# MB_Control.net
KiCad netlist of a schematic drawn in Altium Designer
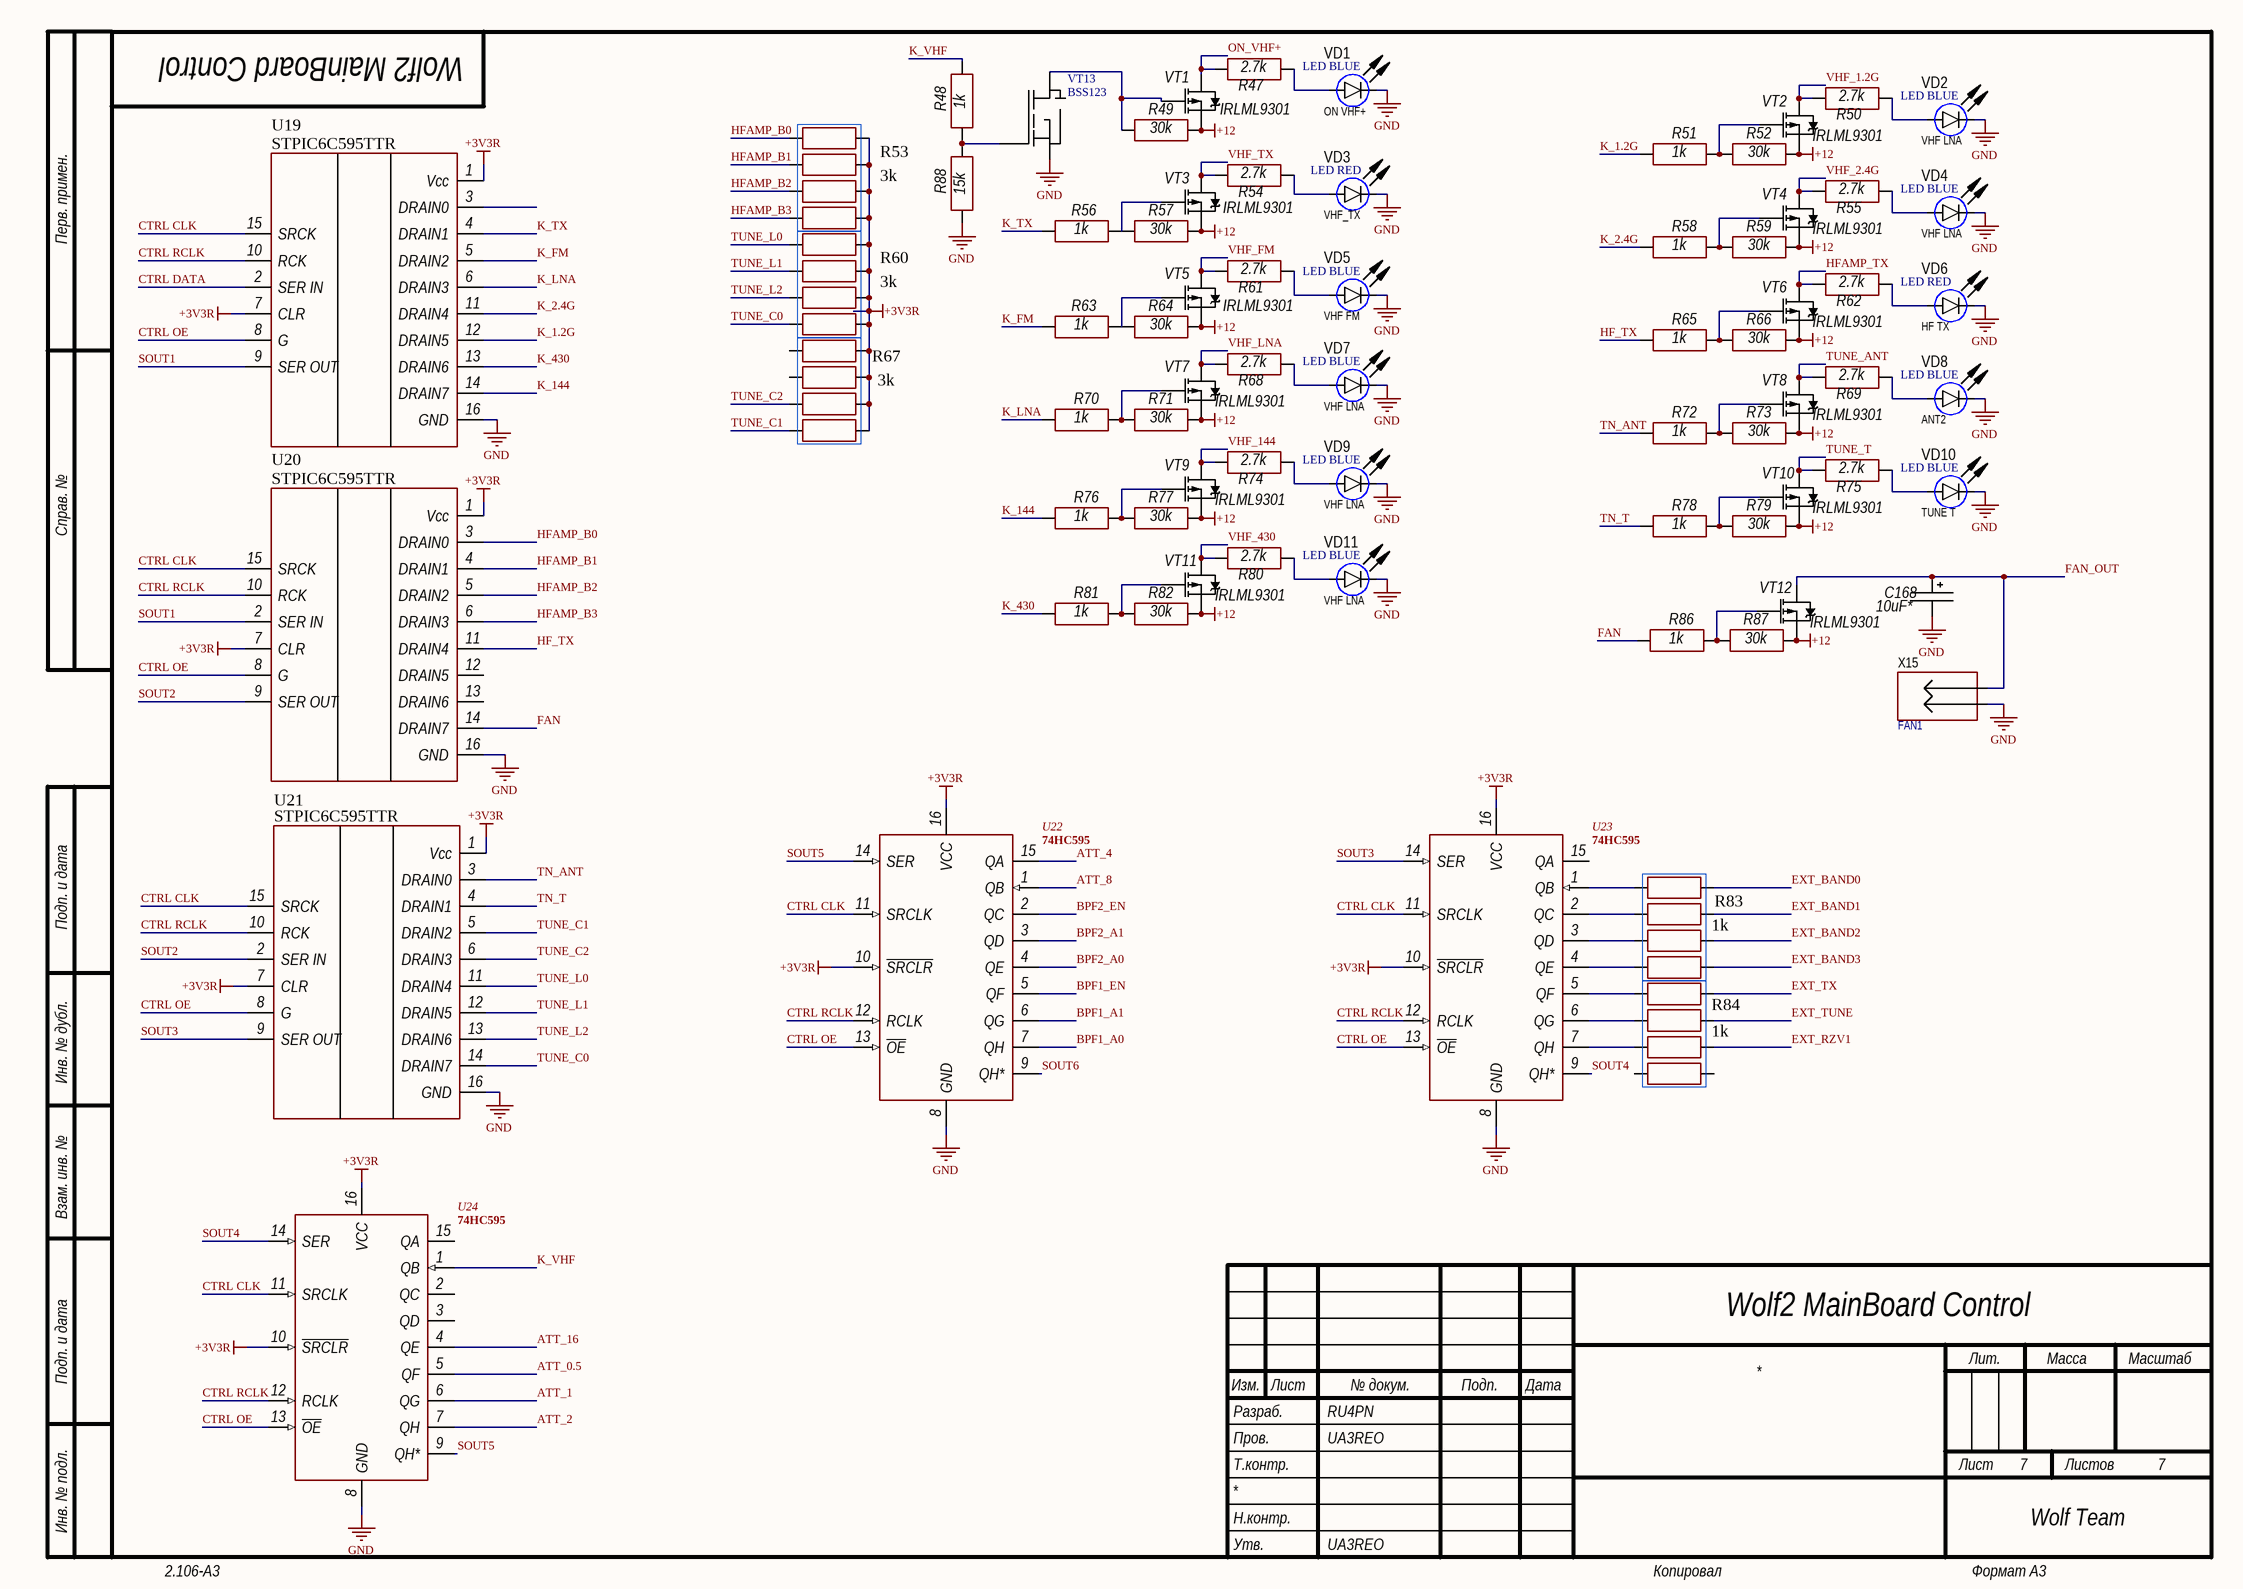
[diagram p0: MB_Control.SchDoc]

(export (version "E")
  (design (tool "Eeschema 10.0.6"))
  (components
    (comp (ref "C168")
      (value "10uF*")
      (footprint "standard:TANTAL_B")
      (libsource (lib "Discrete") (part "TantalCap"))
    )
    (comp (ref "R47")
      (value "2.7k")
      (footprint "standard:CH0805R")
      (libsource (lib "Discrete") (part "Resistor"))
    )
    (comp (ref "R48") (value "1k") (footprint "standard:CH0805R") (libsource (lib "") (part "Resistor_1")))
    (comp (ref "R49")
      (value "30k")
      (footprint "standard:CH0805R")
      (libsource (lib "Discrete") (part "Resistor"))
    )
    (comp (ref "R50")
      (value "2.7k")
      (footprint "standard:CH0805R")
      (libsource (lib "Discrete") (part "Resistor"))
    )
    (comp (ref "R51")
      (value "1k")
      (footprint "standard:CH0805R")
      (libsource (lib "Discrete") (part "Resistor"))
    )
    (comp (ref "R52")
      (value "30k")
      (footprint "standard:CH0805R")
      (libsource (lib "Discrete") (part "Resistor"))
    )
    (comp (ref "R53") (value "3k") (footprint "CAT16") (libsource (lib "") (part "CAT10-0804_1")))
    (comp (ref "R54")
      (value "2.7k")
      (footprint "standard:CH0805R")
      (libsource (lib "Discrete") (part "Resistor"))
    )
    (comp (ref "R55")
      (value "2.7k")
      (footprint "standard:CH0805R")
      (libsource (lib "Discrete") (part "Resistor"))
    )
    (comp (ref "R56")
      (value "1k")
      (footprint "standard:CH0805R")
      (libsource (lib "Discrete") (part "Resistor"))
    )
    (comp (ref "R57")
      (value "30k")
      (footprint "standard:CH0805R")
      (libsource (lib "Discrete") (part "Resistor"))
    )
    (comp (ref "R58")
      (value "1k")
      (footprint "standard:CH0805R")
      (libsource (lib "Discrete") (part "Resistor"))
    )
    (comp (ref "R59")
      (value "30k")
      (footprint "standard:CH0805R")
      (libsource (lib "Discrete") (part "Resistor"))
    )
    (comp (ref "R60") (value "3k") (footprint "CAT16") (libsource (lib "Discrete") (part "CAT10-0804")))
    (comp (ref "R61")
      (value "2.7k")
      (footprint "standard:CH0805R")
      (libsource (lib "Discrete") (part "Resistor"))
    )
    (comp (ref "R62")
      (value "2.7k")
      (footprint "standard:CH0805R")
      (libsource (lib "Discrete") (part "Resistor"))
    )
    (comp (ref "R63")
      (value "1k")
      (footprint "standard:CH0805R")
      (libsource (lib "Discrete") (part "Resistor"))
    )
    (comp (ref "R64")
      (value "30k")
      (footprint "standard:CH0805R")
      (libsource (lib "Discrete") (part "Resistor"))
    )
    (comp (ref "R65")
      (value "1k")
      (footprint "standard:CH0805R")
      (libsource (lib "Discrete") (part "Resistor"))
    )
    (comp (ref "R66")
      (value "30k")
      (footprint "standard:CH0805R")
      (libsource (lib "Discrete") (part "Resistor"))
    )
    (comp (ref "R67") (value "3k") (footprint "CAT16") (libsource (lib "") (part "CAT10-0804_1")))
    (comp (ref "R68")
      (value "2.7k")
      (footprint "standard:CH0805R")
      (libsource (lib "Discrete") (part "Resistor"))
    )
    (comp (ref "R69")
      (value "2.7k")
      (footprint "standard:CH0805R")
      (libsource (lib "Discrete") (part "Resistor"))
    )
    (comp (ref "R70")
      (value "1k")
      (footprint "standard:CH0805R")
      (libsource (lib "Discrete") (part "Resistor"))
    )
    (comp (ref "R71")
      (value "30k")
      (footprint "standard:CH0805R")
      (libsource (lib "Discrete") (part "Resistor"))
    )
    (comp (ref "R72")
      (value "1k")
      (footprint "standard:CH0805R")
      (libsource (lib "Discrete") (part "Resistor"))
    )
    (comp (ref "R73")
      (value "30k")
      (footprint "standard:CH0805R")
      (libsource (lib "Discrete") (part "Resistor"))
    )
    (comp (ref "R74")
      (value "2.7k")
      (footprint "standard:CH0805R")
      (libsource (lib "Discrete") (part "Resistor"))
    )
    (comp (ref "R75")
      (value "2.7k")
      (footprint "standard:CH0805R")
      (libsource (lib "Discrete") (part "Resistor"))
    )
    (comp (ref "R76")
      (value "1k")
      (footprint "standard:CH0805R")
      (libsource (lib "Discrete") (part "Resistor"))
    )
    (comp (ref "R77")
      (value "30k")
      (footprint "standard:CH0805R")
      (libsource (lib "Discrete") (part "Resistor"))
    )
    (comp (ref "R78")
      (value "1k")
      (footprint "standard:CH0805R")
      (libsource (lib "Discrete") (part "Resistor"))
    )
    (comp (ref "R79")
      (value "30k")
      (footprint "standard:CH0805R")
      (libsource (lib "Discrete") (part "Resistor"))
    )
    (comp (ref "R80")
      (value "2.7k")
      (footprint "standard:CH0805R")
      (libsource (lib "Discrete") (part "Resistor"))
    )
    (comp (ref "R81")
      (value "1k")
      (footprint "standard:CH0805R")
      (libsource (lib "Discrete") (part "Resistor"))
    )
    (comp (ref "R82")
      (value "30k")
      (footprint "standard:CH0805R")
      (libsource (lib "Discrete") (part "Resistor"))
    )
    (comp (ref "R83") (value "1k") (footprint "CAT16") (libsource (lib "") (part "CAT10-0804_1")))
    (comp (ref "R84") (value "1k") (footprint "CAT16") (libsource (lib "") (part "CAT10-0804_1")))
    (comp (ref "R86")
      (value "1k")
      (footprint "standard:CH0805R")
      (libsource (lib "Discrete") (part "Resistor"))
    )
    (comp (ref "R87")
      (value "30k")
      (footprint "standard:CH0805R")
      (libsource (lib "Discrete") (part "Resistor"))
    )
    (comp (ref "R88") (value "15k") (footprint "standard:CH0805R") (libsource (lib "") (part "Resistor_1")))
    (comp (ref "U19")
      (value "STPIC6C595TTR")
      (footprint "16-TSOP")
      (libsource (lib "") (part "STPIC6C595TTR_1"))
    )
    (comp (ref "U20")
      (value "STPIC6C595TTR")
      (footprint "16-TSOP")
      (libsource (lib "Digital") (part "STPIC6C595TTR"))
    )
    (comp (ref "U21")
      (value "STPIC6C595TTR")
      (footprint "16-TSOP")
      (libsource (lib "Digital") (part "STPIC6C595TTR"))
    )
    (comp (ref "U22") (value "74HC595") (footprint "16-SO") (libsource (lib "Digital") (part "HC595")))
    (comp (ref "U23") (value "74HC595") (footprint "16-SO") (libsource (lib "Digital") (part "HC595")))
    (comp (ref "U24") (value "74HC595") (footprint "16-SO") (libsource (lib "Digital") (part "HC595")))
    (comp (ref "VD1")
      (value "LED BLUE")
      (footprint "StandardCase:LED: 0805B")
      (fields
        (field (name "VALUEMANUFACTURERPARTNUMBER") "LED, *, *, *, -55...+150°C")
        (field (name "COLOR") "ON VHF+")
      )
      (libsource (lib "Diode") (part "LED_single"))
    )
    (comp (ref "VD2")
      (value "LED BLUE")
      (footprint "StandardCase:LED: 0805B")
      (fields
        (field (name "VALUEMANUFACTURERPARTNUMBER") "LED, *, *, *, -55...+150°C")
        (field (name "COLOR") "VHF LNA")
      )
      (libsource (lib "") (part "LED_single_2"))
    )
    (comp (ref "VD3")
      (value "LED RED")
      (footprint "StandardCase:LED: 0805R")
      (fields
        (field (name "VALUEMANUFACTURERPARTNUMBER") "LED, *, *, *, -55...+150°C")
        (field (name "COLOR") "VHF_TX")
      )
      (libsource (lib "Diode") (part "LED_single"))
    )
    (comp (ref "VD4")
      (value "LED BLUE")
      (footprint "StandardCase:LED: 0805B")
      (fields
        (field (name "VALUEMANUFACTURERPARTNUMBER") "LED, *, *, *, -55...+150°C")
        (field (name "COLOR") "VHF LNA")
      )
      (libsource (lib "") (part "LED_single_2"))
    )
    (comp (ref "VD5")
      (value "LED BLUE")
      (footprint "StandardCase:LED: 0805B")
      (fields
        (field (name "VALUEMANUFACTURERPARTNUMBER") "LED, *, *, *, -55...+150°C")
        (field (name "COLOR") "VHF FM")
      )
      (libsource (lib "Diode") (part "LED_single"))
    )
    (comp (ref "VD6")
      (value "LED RED")
      (footprint "StandardCase:LED: 0805R")
      (fields
        (field (name "VALUEMANUFACTURERPARTNUMBER") "LED, *, *, *, -55...+150°C")
        (field (name "COLOR") "HF TX")
      )
      (libsource (lib "") (part "LED_single_1"))
    )
    (comp (ref "VD7")
      (value "LED BLUE")
      (footprint "StandardCase:LED: 0805B")
      (fields
        (field (name "VALUEMANUFACTURERPARTNUMBER") "LED, *, *, *, -55...+150°C")
        (field (name "COLOR") "VHF LNA")
      )
      (libsource (lib "Diode") (part "LED_single"))
    )
    (comp (ref "VD8")
      (value "LED BLUE")
      (footprint "StandardCase:LED: 0805B")
      (fields
        (field (name "VALUEMANUFACTURERPARTNUMBER") "LED, *, *, *, -55...+150°C")
        (field (name "COLOR") "ANT2")
      )
      (libsource (lib "") (part "LED_single_2"))
    )
    (comp (ref "VD9")
      (value "LED BLUE")
      (footprint "StandardCase:LED: 0805B")
      (fields
        (field (name "VALUEMANUFACTURERPARTNUMBER") "LED, *, *, *, -55...+150°C")
        (field (name "COLOR") "VHF LNA")
      )
      (libsource (lib "Diode") (part "LED_single"))
    )
    (comp (ref "VD10")
      (value "LED BLUE")
      (footprint "StandardCase:LED: 0805B")
      (fields
        (field (name "VALUEMANUFACTURERPARTNUMBER") "LED, *, *, *, -55...+150°C")
        (field (name "COLOR") "TUNE T")
      )
      (libsource (lib "") (part "LED_single_2"))
    )
    (comp (ref "VD11")
      (value "LED BLUE")
      (footprint "StandardCase:LED: 0805B")
      (fields
        (field (name "VALUEMANUFACTURERPARTNUMBER") "LED, *, *, *, -55...+150°C")
        (field (name "COLOR") "VHF LNA")
      )
      (libsource (lib "Diode") (part "LED_single"))
    )
    (comp (ref "VT1")
      (value "IRLML9301")
      (footprint "standard:SOT23_132")
      (description "Mosfet")
      (libsource (lib "") (part "IRLML9301_1"))
    )
    (comp (ref "VT2")
      (value "IRLML9301")
      (footprint "standard:SOT23_132")
      (description "Mosfet")
      (libsource (lib "Transistor") (part "IRLML9301"))
    )
    (comp (ref "VT3")
      (value "IRLML9301")
      (footprint "standard:SOT23_132")
      (description "Mosfet")
      (libsource (lib "") (part "IRLML9301_1"))
    )
    (comp (ref "VT4")
      (value "IRLML9301")
      (footprint "standard:SOT23_132")
      (description "Mosfet")
      (libsource (lib "Transistor") (part "IRLML9301"))
    )
    (comp (ref "VT5")
      (value "IRLML9301")
      (footprint "standard:SOT23_132")
      (description "Mosfet")
      (libsource (lib "") (part "IRLML9301_1"))
    )
    (comp (ref "VT6")
      (value "IRLML9301")
      (footprint "standard:SOT23_132")
      (description "Mosfet")
      (libsource (lib "Transistor") (part "IRLML9301"))
    )
    (comp (ref "VT7")
      (value "IRLML9301")
      (footprint "standard:SOT23_132")
      (description "Mosfet")
      (libsource (lib "") (part "IRLML9301_1"))
    )
    (comp (ref "VT8")
      (value "IRLML9301")
      (footprint "standard:SOT23_132")
      (description "Mosfet")
      (libsource (lib "Transistor") (part "IRLML9301"))
    )
    (comp (ref "VT9")
      (value "IRLML9301")
      (footprint "standard:SOT23_132")
      (description "Mosfet")
      (libsource (lib "") (part "IRLML9301_1"))
    )
    (comp (ref "VT10")
      (value "IRLML9301")
      (footprint "standard:SOT23_132")
      (description "Mosfet")
      (libsource (lib "Transistor") (part "IRLML9301"))
    )
    (comp (ref "VT11")
      (value "IRLML9301")
      (footprint "standard:SOT23_132")
      (description "Mosfet")
      (libsource (lib "") (part "IRLML9301_1"))
    )
    (comp (ref "VT12")
      (value "IRLML9301")
      (footprint "standard:SOT23_132")
      (description "Mosfet")
      (libsource (lib "Transistor") (part "IRLML9301"))
    )
    (comp (ref "VT13")
      (value "BSS123")
      (footprint "SOT23_132")
      (libsource (lib "Transistor") (part "BSS123"))
    )
    (comp (ref "X15")
      (value "FAN1")
      (footprint "CON: CWF-2")
      (libsource (lib "Connectors") (part "Component-2pin"))
    )
  )
  (nets
    (net (code "1") (name "+3V3R") (class "Default")
      (node (ref "R53") (pin "5") (pinfunction "5_5") (pintype "passive"))
      (node (ref "R53") (pin "6") (pinfunction "6_6") (pintype "passive"))
      (node (ref "R53") (pin "7") (pinfunction "7_7") (pintype "passive"))
      (node (ref "R53") (pin "8") (pinfunction "8_8") (pintype "passive"))
      (node (ref "R60") (pin "5") (pinfunction "5_5") (pintype "passive"))
      (node (ref "R60") (pin "6") (pinfunction "6_6") (pintype "passive"))
      (node (ref "R60") (pin "7") (pinfunction "7_7") (pintype "passive"))
      (node (ref "R60") (pin "8") (pinfunction "8_8") (pintype "passive"))
      (node (ref "R67") (pin "5") (pinfunction "5_5") (pintype "passive"))
      (node (ref "R67") (pin "6") (pinfunction "6_6") (pintype "passive"))
      (node (ref "R67") (pin "7") (pinfunction "7_7") (pintype "passive"))
      (node (ref "R67") (pin "8") (pinfunction "8_8") (pintype "passive"))
      (node (ref "U19") (pin "1") (pinfunction "Vcc_1") (pintype "passive"))
      (node (ref "U19") (pin "7") (pinfunction "CLR_7") (pintype "passive"))
      (node (ref "U20") (pin "1") (pinfunction "Vcc_1") (pintype "passive"))
      (node (ref "U20") (pin "7") (pinfunction "CLR_7") (pintype "passive"))
      (node (ref "U21") (pin "1") (pinfunction "Vcc_1") (pintype "passive"))
      (node (ref "U21") (pin "7") (pinfunction "CLR_7") (pintype "passive"))
      (node (ref "U22") (pin "10") (pinfunction "~{SRCLR}_10") (pintype "input"))
      (node (ref "U22") (pin "16") (pinfunction "VCC_16") (pintype "passive"))
      (node (ref "U23") (pin "10") (pinfunction "~{SRCLR}_10") (pintype "input"))
      (node (ref "U23") (pin "16") (pinfunction "VCC_16") (pintype "passive"))
      (node (ref "U24") (pin "10") (pinfunction "~{SRCLR}_10") (pintype "input"))
      (node (ref "U24") (pin "16") (pinfunction "VCC_16") (pintype "passive"))
    )
    (net (code "2") (name "+12") (class "Default")
      (node (ref "R49") (pin "1") (pinfunction "1_1") (pintype "passive"))
      (node (ref "R52") (pin "1") (pinfunction "1_1") (pintype "passive"))
      (node (ref "R57") (pin "1") (pinfunction "1_1") (pintype "passive"))
      (node (ref "R59") (pin "1") (pinfunction "1_1") (pintype "passive"))
      (node (ref "R64") (pin "1") (pinfunction "1_1") (pintype "passive"))
      (node (ref "R66") (pin "1") (pinfunction "1_1") (pintype "passive"))
      (node (ref "R71") (pin "1") (pinfunction "1_1") (pintype "passive"))
      (node (ref "R73") (pin "1") (pinfunction "1_1") (pintype "passive"))
      (node (ref "R77") (pin "1") (pinfunction "1_1") (pintype "passive"))
      (node (ref "R79") (pin "1") (pinfunction "1_1") (pintype "passive"))
      (node (ref "R82") (pin "1") (pinfunction "1_1") (pintype "passive"))
      (node (ref "R87") (pin "1") (pinfunction "1_1") (pintype "passive"))
      (node (ref "VT1") (pin "2") (pinfunction "S_2") (pintype "passive"))
      (node (ref "VT10") (pin "2") (pinfunction "S_2") (pintype "passive"))
      (node (ref "VT11") (pin "2") (pinfunction "S_2") (pintype "passive"))
      (node (ref "VT12") (pin "2") (pinfunction "S_2") (pintype "passive"))
      (node (ref "VT2") (pin "2") (pinfunction "S_2") (pintype "passive"))
      (node (ref "VT3") (pin "2") (pinfunction "S_2") (pintype "passive"))
      (node (ref "VT4") (pin "2") (pinfunction "S_2") (pintype "passive"))
      (node (ref "VT5") (pin "2") (pinfunction "S_2") (pintype "passive"))
      (node (ref "VT6") (pin "2") (pinfunction "S_2") (pintype "passive"))
      (node (ref "VT7") (pin "2") (pinfunction "S_2") (pintype "passive"))
      (node (ref "VT8") (pin "2") (pinfunction "S_2") (pintype "passive"))
      (node (ref "VT9") (pin "2") (pinfunction "S_2") (pintype "passive"))
    )
    (net (code "3") (name "/ATT_0.5") (class "Default")
      (node (ref "U24") (pin "5") (pinfunction "QF_5") (pintype "passive"))
    )
    (net (code "4") (name "/ATT_1") (class "Default")
      (node (ref "U24") (pin "6") (pinfunction "QG_6") (pintype "passive"))
    )
    (net (code "5") (name "/ATT_2") (class "Default")
      (node (ref "U24") (pin "7") (pinfunction "QH_7") (pintype "passive"))
    )
    (net (code "6") (name "/ATT_4") (class "Default")
      (node (ref "U22") (pin "15") (pinfunction "QA_15") (pintype "passive"))
    )
    (net (code "7") (name "/ATT_8") (class "Default")
      (node (ref "U22") (pin "1") (pinfunction "QB_1") (pintype "input"))
    )
    (net (code "8") (name "/ATT_16") (class "Default")
      (node (ref "U24") (pin "4") (pinfunction "QE_4") (pintype "passive"))
    )
    (net (code "9") (name "/BPF1_A0") (class "Default")
      (node (ref "U22") (pin "7") (pinfunction "QH_7") (pintype "passive"))
    )
    (net (code "10") (name "/BPF1_A1") (class "Default")
      (node (ref "U22") (pin "6") (pinfunction "QG_6") (pintype "passive"))
    )
    (net (code "11") (name "/BPF1_EN") (class "Default")
      (node (ref "U22") (pin "5") (pinfunction "QF_5") (pintype "passive"))
    )
    (net (code "12") (name "/BPF2_A0") (class "Default")
      (node (ref "U22") (pin "4") (pinfunction "QE_4") (pintype "passive"))
    )
    (net (code "13") (name "/BPF2_A1") (class "Default")
      (node (ref "U22") (pin "3") (pinfunction "QD_3") (pintype "passive"))
    )
    (net (code "14") (name "/BPF2_EN") (class "Default")
      (node (ref "U22") (pin "2") (pinfunction "QC_2") (pintype "passive"))
    )
    (net (code "15") (name "/CTRL CLK") (class "Default")
      (node (ref "U19") (pin "15") (pinfunction "SRCK_15") (pintype "passive"))
      (node (ref "U20") (pin "15") (pinfunction "SRCK_15") (pintype "passive"))
      (node (ref "U21") (pin "15") (pinfunction "SRCK_15") (pintype "passive"))
      (node (ref "U22") (pin "11") (pinfunction "SRCLK_11") (pintype "input"))
      (node (ref "U23") (pin "11") (pinfunction "SRCLK_11") (pintype "input"))
      (node (ref "U24") (pin "11") (pinfunction "SRCLK_11") (pintype "input"))
    )
    (net (code "16") (name "/CTRL DATA") (class "Default")
      (node (ref "U19") (pin "2") (pinfunction "SER_IN_2") (pintype "passive"))
    )
    (net (code "17") (name "/CTRL OE") (class "Default")
      (node (ref "U19") (pin "8") (pinfunction "G_8") (pintype "passive"))
      (node (ref "U20") (pin "8") (pinfunction "G_8") (pintype "passive"))
      (node (ref "U21") (pin "8") (pinfunction "G_8") (pintype "passive"))
      (node (ref "U22") (pin "13") (pinfunction "~{OE}_13") (pintype "input"))
      (node (ref "U23") (pin "13") (pinfunction "~{OE}_13") (pintype "input"))
      (node (ref "U24") (pin "13") (pinfunction "~{OE}_13") (pintype "input"))
    )
    (net (code "18") (name "/CTRL RCLK") (class "Default")
      (node (ref "U19") (pin "10") (pinfunction "RCK_10") (pintype "passive"))
      (node (ref "U20") (pin "10") (pinfunction "RCK_10") (pintype "passive"))
      (node (ref "U21") (pin "10") (pinfunction "RCK_10") (pintype "passive"))
      (node (ref "U22") (pin "12") (pinfunction "RCLK_12") (pintype "input"))
      (node (ref "U23") (pin "12") (pinfunction "RCLK_12") (pintype "input"))
      (node (ref "U24") (pin "12") (pinfunction "RCLK_12") (pintype "input"))
    )
    (net (code "19") (name "/EXT_BAND0") (class "Default")
      (node (ref "R83") (pin "5") (pinfunction "5_5") (pintype "passive"))
    )
    (net (code "20") (name "/EXT_BAND1") (class "Default")
      (node (ref "R83") (pin "6") (pinfunction "6_6") (pintype "passive"))
    )
    (net (code "21") (name "/EXT_BAND2") (class "Default")
      (node (ref "R83") (pin "7") (pinfunction "7_7") (pintype "passive"))
    )
    (net (code "22") (name "/EXT_BAND3") (class "Default")
      (node (ref "R83") (pin "8") (pinfunction "8_8") (pintype "passive"))
    )
    (net (code "23") (name "/EXT_RZV1") (class "Default")
      (node (ref "R84") (pin "7") (pinfunction "7_7") (pintype "passive"))
    )
    (net (code "24") (name "/EXT_TUNE") (class "Default")
      (node (ref "R84") (pin "6") (pinfunction "6_6") (pintype "passive"))
    )
    (net (code "25") (name "/EXT_TX") (class "Default")
      (node (ref "R84") (pin "5") (pinfunction "5_5") (pintype "passive"))
    )
    (net (code "26") (name "/FAN") (class "Default")
      (node (ref "R86") (pin "2") (pinfunction "2_2") (pintype "passive"))
      (node (ref "U20") (pin "14") (pinfunction "DRAIN7_14") (pintype "passive"))
    )
    (net (code "27") (name "/FAN_OUT") (class "Default")
      (node (ref "C168") (pin "1") (pinfunction "1_1") (pintype "power_in"))
      (node (ref "VT12") (pin "3") (pinfunction "D_3") (pintype "passive"))
      (node (ref "X15") (pin "1") (pinfunction "1_1") (pintype "passive"))
    )
    (net (code "28") (name "/HFAMP_B0") (class "Default")
      (node (ref "R53") (pin "1") (pinfunction "1_1") (pintype "passive"))
      (node (ref "U20") (pin "3") (pinfunction "DRAIN0_3") (pintype "passive"))
    )
    (net (code "29") (name "/HFAMP_B1") (class "Default")
      (node (ref "R53") (pin "2") (pinfunction "2_2") (pintype "passive"))
      (node (ref "U20") (pin "4") (pinfunction "DRAIN1_4") (pintype "passive"))
    )
    (net (code "30") (name "/HFAMP_B2") (class "Default")
      (node (ref "R53") (pin "3") (pinfunction "3_3") (pintype "passive"))
      (node (ref "U20") (pin "5") (pinfunction "DRAIN2_5") (pintype "passive"))
    )
    (net (code "31") (name "/HFAMP_B3") (class "Default")
      (node (ref "R53") (pin "4") (pinfunction "4_4") (pintype "passive"))
      (node (ref "U20") (pin "6") (pinfunction "DRAIN3_6") (pintype "passive"))
    )
    (net (code "32") (name "/HFAMP_TX") (class "Default")
      (node (ref "R62") (pin "2") (pinfunction "2_2") (pintype "passive"))
      (node (ref "VT6") (pin "3") (pinfunction "D_3") (pintype "passive"))
    )
    (net (code "33") (name "/HF_TX") (class "Default")
      (node (ref "R65") (pin "2") (pinfunction "2_2") (pintype "passive"))
      (node (ref "U20") (pin "11") (pinfunction "DRAIN4_11") (pintype "passive"))
    )
    (net (code "34") (name "/K_1.2G") (class "Default")
      (node (ref "R51") (pin "2") (pinfunction "2_2") (pintype "passive"))
      (node (ref "U19") (pin "12") (pinfunction "DRAIN5_12") (pintype "passive"))
    )
    (net (code "35") (name "/K_2.4G") (class "Default")
      (node (ref "R58") (pin "2") (pinfunction "2_2") (pintype "passive"))
      (node (ref "U19") (pin "11") (pinfunction "DRAIN4_11") (pintype "passive"))
    )
    (net (code "36") (name "/K_144") (class "Default")
      (node (ref "R76") (pin "2") (pinfunction "2_2") (pintype "passive"))
      (node (ref "U19") (pin "14") (pinfunction "DRAIN7_14") (pintype "passive"))
    )
    (net (code "37") (name "/K_430") (class "Default")
      (node (ref "R81") (pin "2") (pinfunction "2_2") (pintype "passive"))
      (node (ref "U19") (pin "13") (pinfunction "DRAIN6_13") (pintype "passive"))
    )
    (net (code "38") (name "/K_FM") (class "Default")
      (node (ref "R63") (pin "2") (pinfunction "2_2") (pintype "passive"))
      (node (ref "U19") (pin "5") (pinfunction "DRAIN2_5") (pintype "passive"))
    )
    (net (code "39") (name "/K_LNA") (class "Default")
      (node (ref "R70") (pin "2") (pinfunction "2_2") (pintype "passive"))
      (node (ref "U19") (pin "6") (pinfunction "DRAIN3_6") (pintype "passive"))
    )
    (net (code "40") (name "/K_TX") (class "Default")
      (node (ref "R56") (pin "2") (pinfunction "2_2") (pintype "passive"))
      (node (ref "U19") (pin "4") (pinfunction "DRAIN1_4") (pintype "passive"))
    )
    (net (code "41") (name "/K_VHF") (class "Default")
      (node (ref "R48") (pin "1") (pinfunction "1_1") (pintype "passive"))
      (node (ref "U24") (pin "1") (pinfunction "QB_1") (pintype "input"))
    )
    (net (code "42") (name "/ON_VHF+") (class "Default")
      (node (ref "R47") (pin "2") (pinfunction "2_2") (pintype "passive"))
      (node (ref "VT1") (pin "3") (pinfunction "D_3") (pintype "passive"))
    )
    (net (code "43") (name "/SOUT1") (class "Default")
      (node (ref "U19") (pin "9") (pinfunction "SER_OUT_9") (pintype "passive"))
      (node (ref "U20") (pin "2") (pinfunction "SER_IN_2") (pintype "passive"))
    )
    (net (code "44") (name "/SOUT2") (class "Default")
      (node (ref "U20") (pin "9") (pinfunction "SER_OUT_9") (pintype "passive"))
      (node (ref "U21") (pin "2") (pinfunction "SER_IN_2") (pintype "passive"))
    )
    (net (code "45") (name "/SOUT3") (class "Default")
      (node (ref "U21") (pin "9") (pinfunction "SER_OUT_9") (pintype "passive"))
      (node (ref "U23") (pin "14") (pinfunction "SER_14") (pintype "input"))
    )
    (net (code "46") (name "/SOUT4") (class "Default")
      (node (ref "U23") (pin "9") (pinfunction "QH*_9") (pintype "passive"))
      (node (ref "U24") (pin "14") (pinfunction "SER_14") (pintype "input"))
    )
    (net (code "47") (name "/SOUT5") (class "Default")
      (node (ref "U22") (pin "14") (pinfunction "SER_14") (pintype "input"))
      (node (ref "U24") (pin "9") (pinfunction "QH*_9") (pintype "passive"))
    )
    (net (code "48") (name "/SOUT6") (class "Default")
      (node (ref "U22") (pin "9") (pinfunction "QH*_9") (pintype "passive"))
    )
    (net (code "49") (name "/TN_ANT") (class "Default")
      (node (ref "R72") (pin "2") (pinfunction "2_2") (pintype "passive"))
      (node (ref "U21") (pin "3") (pinfunction "DRAIN0_3") (pintype "passive"))
    )
    (net (code "50") (name "/TN_T") (class "Default")
      (node (ref "R78") (pin "2") (pinfunction "2_2") (pintype "passive"))
      (node (ref "U21") (pin "4") (pinfunction "DRAIN1_4") (pintype "passive"))
    )
    (net (code "51") (name "/TUNE_ANT") (class "Default")
      (node (ref "R69") (pin "2") (pinfunction "2_2") (pintype "passive"))
      (node (ref "VT8") (pin "3") (pinfunction "D_3") (pintype "passive"))
    )
    (net (code "52") (name "/TUNE_C0") (class "Default")
      (node (ref "R60") (pin "4") (pinfunction "4_4") (pintype "passive"))
      (node (ref "U21") (pin "14") (pinfunction "DRAIN7_14") (pintype "passive"))
    )
    (net (code "53") (name "/TUNE_C1") (class "Default")
      (node (ref "R67") (pin "4") (pinfunction "4_4") (pintype "passive"))
      (node (ref "U21") (pin "5") (pinfunction "DRAIN2_5") (pintype "passive"))
    )
    (net (code "54") (name "/TUNE_C2") (class "Default")
      (node (ref "R67") (pin "3") (pinfunction "3_3") (pintype "passive"))
      (node (ref "U21") (pin "6") (pinfunction "DRAIN3_6") (pintype "passive"))
    )
    (net (code "55") (name "/TUNE_L0") (class "Default")
      (node (ref "R60") (pin "1") (pinfunction "1_1") (pintype "passive"))
      (node (ref "U21") (pin "11") (pinfunction "DRAIN4_11") (pintype "passive"))
    )
    (net (code "56") (name "/TUNE_L1") (class "Default")
      (node (ref "R60") (pin "2") (pinfunction "2_2") (pintype "passive"))
      (node (ref "U21") (pin "12") (pinfunction "DRAIN5_12") (pintype "passive"))
    )
    (net (code "57") (name "/TUNE_L2") (class "Default")
      (node (ref "R60") (pin "3") (pinfunction "3_3") (pintype "passive"))
      (node (ref "U21") (pin "13") (pinfunction "DRAIN6_13") (pintype "passive"))
    )
    (net (code "58") (name "/TUNE_T") (class "Default")
      (node (ref "R75") (pin "2") (pinfunction "2_2") (pintype "passive"))
      (node (ref "VT10") (pin "3") (pinfunction "D_3") (pintype "passive"))
    )
    (net (code "59") (name "/VHF_1.2G") (class "Default")
      (node (ref "R50") (pin "2") (pinfunction "2_2") (pintype "passive"))
      (node (ref "VT2") (pin "3") (pinfunction "D_3") (pintype "passive"))
    )
    (net (code "60") (name "/VHF_2.4G") (class "Default")
      (node (ref "R55") (pin "2") (pinfunction "2_2") (pintype "passive"))
      (node (ref "VT4") (pin "3") (pinfunction "D_3") (pintype "passive"))
    )
    (net (code "61") (name "/VHF_144") (class "Default")
      (node (ref "R74") (pin "2") (pinfunction "2_2") (pintype "passive"))
      (node (ref "VT9") (pin "3") (pinfunction "D_3") (pintype "passive"))
    )
    (net (code "62") (name "/VHF_430") (class "Default")
      (node (ref "R80") (pin "2") (pinfunction "2_2") (pintype "passive"))
      (node (ref "VT11") (pin "3") (pinfunction "D_3") (pintype "passive"))
    )
    (net (code "63") (name "/VHF_FM") (class "Default")
      (node (ref "R61") (pin "2") (pinfunction "2_2") (pintype "passive"))
      (node (ref "VT5") (pin "3") (pinfunction "D_3") (pintype "passive"))
    )
    (net (code "64") (name "/VHF_LNA") (class "Default")
      (node (ref "R68") (pin "2") (pinfunction "2_2") (pintype "passive"))
      (node (ref "VT7") (pin "3") (pinfunction "D_3") (pintype "passive"))
    )
    (net (code "65") (name "/VHF_TX") (class "Default")
      (node (ref "R54") (pin "2") (pinfunction "2_2") (pintype "passive"))
      (node (ref "VT3") (pin "3") (pinfunction "D_3") (pintype "passive"))
    )
    (net (code "66") (name "GND") (class "Default")
      (node (ref "C168") (pin "2") (pinfunction "2_2") (pintype "power_in"))
      (node (ref "R88") (pin "2") (pinfunction "2_2") (pintype "passive"))
      (node (ref "U19") (pin "16") (pinfunction "GND_16") (pintype "passive"))
      (node (ref "U20") (pin "16") (pinfunction "GND_16") (pintype "passive"))
      (node (ref "U21") (pin "16") (pinfunction "GND_16") (pintype "passive"))
      (node (ref "U22") (pin "8") (pinfunction "GND_8") (pintype "passive"))
      (node (ref "U23") (pin "8") (pinfunction "GND_8") (pintype "passive"))
      (node (ref "U24") (pin "8") (pinfunction "GND_8") (pintype "passive"))
      (node (ref "VD1") (pin "2") (pinfunction "C_2") (pintype "passive"))
      (node (ref "VD10") (pin "2") (pinfunction "C_2") (pintype "passive"))
      (node (ref "VD11") (pin "2") (pinfunction "C_2") (pintype "passive"))
      (node (ref "VD2") (pin "2") (pinfunction "C_2") (pintype "passive"))
      (node (ref "VD3") (pin "2") (pinfunction "C_2") (pintype "passive"))
      (node (ref "VD4") (pin "2") (pinfunction "C_2") (pintype "passive"))
      (node (ref "VD5") (pin "2") (pinfunction "C_2") (pintype "passive"))
      (node (ref "VD6") (pin "2") (pinfunction "C_2") (pintype "passive"))
      (node (ref "VD7") (pin "2") (pinfunction "C_2") (pintype "passive"))
      (node (ref "VD8") (pin "2") (pinfunction "C_2") (pintype "passive"))
      (node (ref "VD9") (pin "2") (pinfunction "C_2") (pintype "passive"))
      (node (ref "VT13") (pin "2") (pinfunction "S_2") (pintype "passive"))
      (node (ref "X15") (pin "2") (pinfunction "2_2") (pintype "passive"))
    )
    (net (code "67") (name "Net-(U23-QB)") (class "Default")
      (node (ref "R83") (pin "1") (pinfunction "1_1") (pintype "passive"))
      (node (ref "U23") (pin "1") (pinfunction "QB_1") (pintype "input"))
    )
    (net (code "68") (name "Net-(U23-QC)") (class "Default")
      (node (ref "R83") (pin "2") (pinfunction "2_2") (pintype "passive"))
      (node (ref "U23") (pin "2") (pinfunction "QC_2") (pintype "passive"))
    )
    (net (code "69") (name "Net-(U23-QD)") (class "Default")
      (node (ref "R83") (pin "3") (pinfunction "3_3") (pintype "passive"))
      (node (ref "U23") (pin "3") (pinfunction "QD_3") (pintype "passive"))
    )
    (net (code "70") (name "Net-(U23-QE)") (class "Default")
      (node (ref "R83") (pin "4") (pinfunction "4_4") (pintype "passive"))
      (node (ref "U23") (pin "4") (pinfunction "QE_4") (pintype "passive"))
    )
    (net (code "71") (name "Net-(U23-QF)") (class "Default")
      (node (ref "R84") (pin "1") (pinfunction "1_1") (pintype "passive"))
      (node (ref "U23") (pin "5") (pinfunction "QF_5") (pintype "passive"))
    )
    (net (code "72") (name "Net-(U23-QG)") (class "Default")
      (node (ref "R84") (pin "2") (pinfunction "2_2") (pintype "passive"))
      (node (ref "U23") (pin "6") (pinfunction "QG_6") (pintype "passive"))
    )
    (net (code "73") (name "Net-(U23-QH)") (class "Default")
      (node (ref "R84") (pin "3") (pinfunction "3_3") (pintype "passive"))
      (node (ref "U23") (pin "7") (pinfunction "QH_7") (pintype "passive"))
    )
    (net (code "74") (name "Net-(VD1-A)") (class "Default")
      (node (ref "R47") (pin "1") (pinfunction "1_1") (pintype "passive"))
      (node (ref "VD1") (pin "1") (pinfunction "A_1") (pintype "passive"))
    )
    (net (code "75") (name "Net-(VD2-A)") (class "Default")
      (node (ref "R50") (pin "1") (pinfunction "1_1") (pintype "passive"))
      (node (ref "VD2") (pin "1") (pinfunction "A_1") (pintype "passive"))
    )
    (net (code "76") (name "Net-(VD3-A)") (class "Default")
      (node (ref "R54") (pin "1") (pinfunction "1_1") (pintype "passive"))
      (node (ref "VD3") (pin "1") (pinfunction "A_1") (pintype "passive"))
    )
    (net (code "77") (name "Net-(VD4-A)") (class "Default")
      (node (ref "R55") (pin "1") (pinfunction "1_1") (pintype "passive"))
      (node (ref "VD4") (pin "1") (pinfunction "A_1") (pintype "passive"))
    )
    (net (code "78") (name "Net-(VD5-A)") (class "Default")
      (node (ref "R61") (pin "1") (pinfunction "1_1") (pintype "passive"))
      (node (ref "VD5") (pin "1") (pinfunction "A_1") (pintype "passive"))
    )
    (net (code "79") (name "Net-(VD6-A)") (class "Default")
      (node (ref "R62") (pin "1") (pinfunction "1_1") (pintype "passive"))
      (node (ref "VD6") (pin "1") (pinfunction "A_1") (pintype "passive"))
    )
    (net (code "80") (name "Net-(VD7-A)") (class "Default")
      (node (ref "R68") (pin "1") (pinfunction "1_1") (pintype "passive"))
      (node (ref "VD7") (pin "1") (pinfunction "A_1") (pintype "passive"))
    )
    (net (code "81") (name "Net-(VD8-A)") (class "Default")
      (node (ref "R69") (pin "1") (pinfunction "1_1") (pintype "passive"))
      (node (ref "VD8") (pin "1") (pinfunction "A_1") (pintype "passive"))
    )
    (net (code "82") (name "Net-(VD9-A)") (class "Default")
      (node (ref "R74") (pin "1") (pinfunction "1_1") (pintype "passive"))
      (node (ref "VD9") (pin "1") (pinfunction "A_1") (pintype "passive"))
    )
    (net (code "83") (name "Net-(VD10-A)") (class "Default")
      (node (ref "R75") (pin "1") (pinfunction "1_1") (pintype "passive"))
      (node (ref "VD10") (pin "1") (pinfunction "A_1") (pintype "passive"))
    )
    (net (code "84") (name "Net-(VD11-A)") (class "Default")
      (node (ref "R80") (pin "1") (pinfunction "1_1") (pintype "passive"))
      (node (ref "VD11") (pin "1") (pinfunction "A_1") (pintype "passive"))
    )
    (net (code "85") (name "Net-(VT1-G)") (class "Default")
      (node (ref "R49") (pin "2") (pinfunction "2_2") (pintype "passive"))
      (node (ref "VT1") (pin "1") (pinfunction "G_1") (pintype "passive"))
      (node (ref "VT13") (pin "3") (pinfunction "D_3") (pintype "passive"))
    )
    (net (code "86") (name "Net-(VT2-G)") (class "Default")
      (node (ref "R51") (pin "1") (pinfunction "1_1") (pintype "passive"))
      (node (ref "R52") (pin "2") (pinfunction "2_2") (pintype "passive"))
      (node (ref "VT2") (pin "1") (pinfunction "G_1") (pintype "passive"))
    )
    (net (code "87") (name "Net-(VT3-G)") (class "Default")
      (node (ref "R56") (pin "1") (pinfunction "1_1") (pintype "passive"))
      (node (ref "R57") (pin "2") (pinfunction "2_2") (pintype "passive"))
      (node (ref "VT3") (pin "1") (pinfunction "G_1") (pintype "passive"))
    )
    (net (code "88") (name "Net-(VT4-G)") (class "Default")
      (node (ref "R58") (pin "1") (pinfunction "1_1") (pintype "passive"))
      (node (ref "R59") (pin "2") (pinfunction "2_2") (pintype "passive"))
      (node (ref "VT4") (pin "1") (pinfunction "G_1") (pintype "passive"))
    )
    (net (code "89") (name "Net-(VT5-G)") (class "Default")
      (node (ref "R63") (pin "1") (pinfunction "1_1") (pintype "passive"))
      (node (ref "R64") (pin "2") (pinfunction "2_2") (pintype "passive"))
      (node (ref "VT5") (pin "1") (pinfunction "G_1") (pintype "passive"))
    )
    (net (code "90") (name "Net-(VT6-G)") (class "Default")
      (node (ref "R65") (pin "1") (pinfunction "1_1") (pintype "passive"))
      (node (ref "R66") (pin "2") (pinfunction "2_2") (pintype "passive"))
      (node (ref "VT6") (pin "1") (pinfunction "G_1") (pintype "passive"))
    )
    (net (code "91") (name "Net-(VT7-G)") (class "Default")
      (node (ref "R70") (pin "1") (pinfunction "1_1") (pintype "passive"))
      (node (ref "R71") (pin "2") (pinfunction "2_2") (pintype "passive"))
      (node (ref "VT7") (pin "1") (pinfunction "G_1") (pintype "passive"))
    )
    (net (code "92") (name "Net-(VT8-G)") (class "Default")
      (node (ref "R72") (pin "1") (pinfunction "1_1") (pintype "passive"))
      (node (ref "R73") (pin "2") (pinfunction "2_2") (pintype "passive"))
      (node (ref "VT8") (pin "1") (pinfunction "G_1") (pintype "passive"))
    )
    (net (code "93") (name "Net-(VT9-G)") (class "Default")
      (node (ref "R76") (pin "1") (pinfunction "1_1") (pintype "passive"))
      (node (ref "R77") (pin "2") (pinfunction "2_2") (pintype "passive"))
      (node (ref "VT9") (pin "1") (pinfunction "G_1") (pintype "passive"))
    )
    (net (code "94") (name "Net-(VT10-G)") (class "Default")
      (node (ref "R78") (pin "1") (pinfunction "1_1") (pintype "passive"))
      (node (ref "R79") (pin "2") (pinfunction "2_2") (pintype "passive"))
      (node (ref "VT10") (pin "1") (pinfunction "G_1") (pintype "passive"))
    )
    (net (code "95") (name "Net-(VT11-G)") (class "Default")
      (node (ref "R81") (pin "1") (pinfunction "1_1") (pintype "passive"))
      (node (ref "R82") (pin "2") (pinfunction "2_2") (pintype "passive"))
      (node (ref "VT11") (pin "1") (pinfunction "G_1") (pintype "passive"))
    )
    (net (code "96") (name "Net-(VT12-G)") (class "Default")
      (node (ref "R86") (pin "1") (pinfunction "1_1") (pintype "passive"))
      (node (ref "R87") (pin "2") (pinfunction "2_2") (pintype "passive"))
      (node (ref "VT12") (pin "1") (pinfunction "G_1") (pintype "passive"))
    )
    (net (code "97") (name "Net-(VT13-G)") (class "Default")
      (node (ref "R48") (pin "2") (pinfunction "2_2") (pintype "passive"))
      (node (ref "R88") (pin "1") (pinfunction "1_1") (pintype "passive"))
      (node (ref "VT13") (pin "1") (pinfunction "G_1") (pintype "passive"))
    )
    (net (code "98") (name "unconnected-(R67-Pad1)") (class "Default")
      (node (ref "R67") (pin "1") (pinfunction "1_1") (pintype "passive"))
    )
    (net (code "99") (name "unconnected-(R67-Pad2)") (class "Default")
      (node (ref "R67") (pin "2") (pinfunction "2_2") (pintype "passive"))
    )
    (net (code "100") (name "unconnected-(R84-Pad4)") (class "Default")
      (node (ref "R84") (pin "4") (pinfunction "4_4") (pintype "passive"))
    )
    (net (code "101") (name "unconnected-(R84-Pad8)") (class "Default")
      (node (ref "R84") (pin "8") (pinfunction "8_8") (pintype "passive"))
    )
    (net (code "102") (name "unconnected-(U19-DRAIN0-Pad3)") (class "Default")
      (node (ref "U19") (pin "3") (pinfunction "DRAIN0_3") (pintype "passive"))
    )
    (net (code "103") (name "unconnected-(U20-DRAIN5-Pad12)") (class "Default")
      (node (ref "U20") (pin "12") (pinfunction "DRAIN5_12") (pintype "passive"))
    )
    (net (code "104") (name "unconnected-(U20-DRAIN6-Pad13)") (class "Default")
      (node (ref "U20") (pin "13") (pinfunction "DRAIN6_13") (pintype "passive"))
    )
    (net (code "105") (name "unconnected-(U23-QA-Pad15)") (class "Default")
      (node (ref "U23") (pin "15") (pinfunction "QA_15") (pintype "passive"))
    )
    (net (code "106") (name "unconnected-(U24-QA-Pad15)") (class "Default")
      (node (ref "U24") (pin "15") (pinfunction "QA_15") (pintype "passive"))
    )
    (net (code "107") (name "unconnected-(U24-QC-Pad2)") (class "Default")
      (node (ref "U24") (pin "2") (pinfunction "QC_2") (pintype "passive"))
    )
    (net (code "108") (name "unconnected-(U24-QD-Pad3)") (class "Default")
      (node (ref "U24") (pin "3") (pinfunction "QD_3") (pintype "passive"))
    )
  )
)
